# RS485_IO.net
KiCad netlist of a schematic drawn in Altium Designer
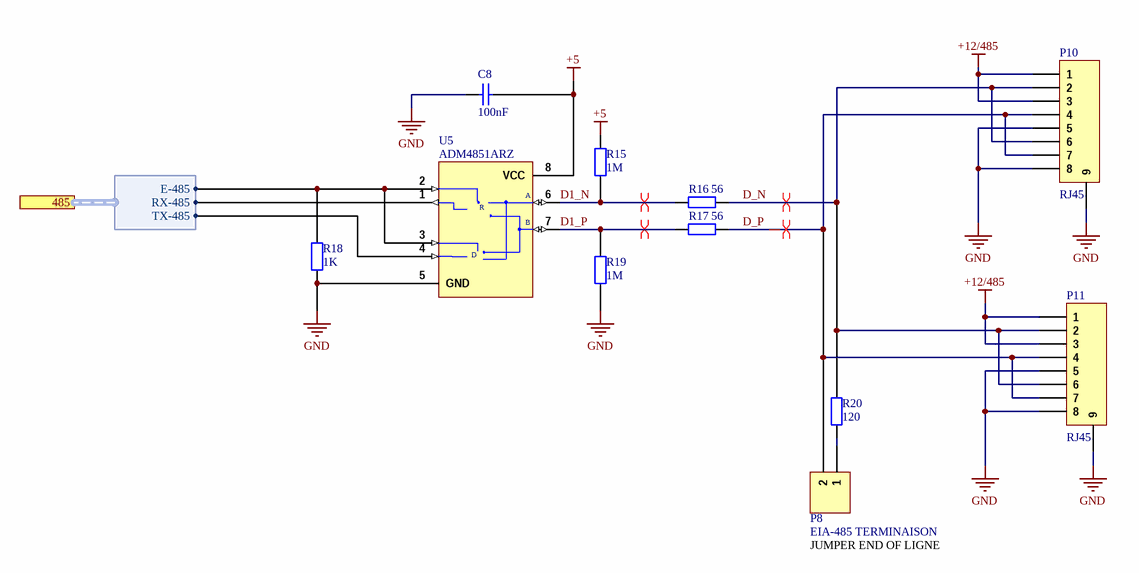
[diagram p0: RS485 IO.SchDoc]

(export (version "E")
  (design (tool "Eeschema 10.0.6"))
  (components
    (comp (ref "C8")
      (value "100nF")
      (footprint "SYLANN:C0805")
      (description "Capacitor")
      (fields
        (field (name "MANUFACTURER") "MULTICOMP")
        (field (name "MANUFACTURER PART NUMBER") "MCCA000296")
      )
      (libsource (lib "BRA") (part "Cap 0805 100nF"))
    )
    (comp (ref "P8")
      (value "EIA-485 TERMINAISON")
      (footprint "M20_1X2")
      (description "Header, 2-Pin")
      (fields
        (field (name "MANUFACTURER") "HARWIN")
        (field (name "MANUFACTURER PART NUMBER") "M20-8770242")
        (field (name "PUBLISHER") "Altium Limited")
      )
      (libsource (lib "Miscellaneous Connectors") (part "Header 2"))
    )
    (comp (ref "P10")
      (value "RJ45")
      (footprint "RJ45_8-5406721-1")
      (description "Header, 8-Pin")
      (fields
        (field (name "MANUFACTURER") "TE CONNECTIVITY / AMP")
        (field (name "MANUFACTURER PART NUMBER") "5406721-1")
      )
      (libsource (lib "MAIN BOARD CERES") (part "Header 8"))
    )
    (comp (ref "P11")
      (value "RJ45")
      (footprint "RJ45_8-5406721-1")
      (description "Header, 8-Pin")
      (fields
        (field (name "MANUFACTURER") "TE CONNECTIVITY / AMP")
        (field (name "MANUFACTURER PART NUMBER") "5406721-1")
      )
      (libsource (lib "MAIN BOARD CERES") (part "Header 8"))
    )
    (comp (ref "R15")
      (value "1M")
      (footprint "R0805")
      (description "Resistor")
      (libsource (lib "BRA") (part "Resistor 0805 1M"))
    )
    (comp (ref "R16")
      (value "56")
      (footprint "R0805")
      (description "Resistor")
      (fields
        (field (name "MANUFACTURER") "MULTICOMP")
        (field (name "MANUFACTURER PART NUMBER") "MC01W0805156R")
      )
      (libsource (lib "BRA") (part "Resistor 0805 56"))
    )
    (comp (ref "R17")
      (value "56")
      (footprint "R0805")
      (description "Resistor")
      (fields
        (field (name "MANUFACTURER") "MULTICOMP")
        (field (name "MANUFACTURER PART NUMBER") "MC01W0805156R")
      )
      (libsource (lib "BRA") (part "Resistor 0805 56"))
    )
    (comp (ref "R18")
      (value "1K")
      (footprint "R0805")
      (description "Resistor")
      (fields
        (field (name "MANUFACTURER") "MULTICOMP")
        (field (name "MANUFACTURER PART NUMBER") "MC0.1W08051%1KFR")
      )
      (libsource (lib "BRA") (part "Resistor 0805 1K"))
    )
    (comp (ref "R19")
      (value "1M")
      (footprint "R0805")
      (description "Resistor")
      (libsource (lib "BRA") (part "Resistor 0805 1M"))
    )
    (comp (ref "R20")
      (value "120")
      (footprint "R0805")
      (description "Resistor")
      (fields
        (field (name "MANUFACTURER") "MULTICOMP")
        (field (name "MANUFACTURER PART NUMBER") "MC01W080516K49")
      )
      (libsource (lib "BRA") (part "Resistor 0805 120"))
    )
    (comp (ref "U5")
      (value "ADM4851ARZ")
      (footprint "SOIC8")
      (description "Low-Power, Slew-Rate-Limited RS-485/RS-422 Transceiver")
      (fields (field (name "MANUFACTURER") "ANALOG DEVICES"))
      (libsource (lib "Maxim Communication Transceiver") (part "MAX485ESA"))
    )
  )
  (nets
    (net (code "2") (name "+5") (class "Default")
      (node (ref "C8") (pin "1") (pinfunction "1_1") (pintype "passive"))
      (node (ref "R15") (pin "2") (pinfunction "2_2") (pintype "passive"))
      (node (ref "U5") (pin "8") (pinfunction "VCC_8") (pintype "power_in"))
    )
    (net (code "3") (name "+12{slash}485") (class "Default")
      (node (ref "P10") (pin "1") (pinfunction "1_1") (pintype "passive"))
      (node (ref "P10") (pin "3") (pinfunction "3_3") (pintype "passive"))
      (node (ref "P11") (pin "1") (pinfunction "1_1") (pintype "passive"))
      (node (ref "P11") (pin "3") (pinfunction "3_3") (pintype "passive"))
    )
    (net (code "4") (name "/D1_N") (class "Default")
      (node (ref "R15") (pin "1") (pinfunction "1_1") (pintype "passive"))
      (node (ref "R16") (pin "1") (pinfunction "1_1") (pintype "passive"))
      (node (ref "U5") (pin "6") (pinfunction "A_6") (pintype "bidirectional"))
    )
    (net (code "5") (name "/D1_P") (class "Default")
      (node (ref "R17") (pin "1") (pinfunction "1_1") (pintype "passive"))
      (node (ref "R19") (pin "2") (pinfunction "2_2") (pintype "passive"))
      (node (ref "U5") (pin "7") (pinfunction "B_7") (pintype "bidirectional"))
    )
    (net (code "6") (name "/D_N") (class "Default")
      (node (ref "P10") (pin "2") (pinfunction "2_2") (pintype "passive"))
      (node (ref "P10") (pin "6") (pinfunction "6_6") (pintype "passive"))
      (node (ref "P11") (pin "2") (pinfunction "2_2") (pintype "passive"))
      (node (ref "P11") (pin "6") (pinfunction "6_6") (pintype "passive"))
      (node (ref "R16") (pin "2") (pinfunction "2_2") (pintype "passive"))
      (node (ref "R20") (pin "2") (pinfunction "2_2") (pintype "passive"))
    )
    (net (code "7") (name "/D_P") (class "Default")
      (node (ref "P10") (pin "4") (pinfunction "4_4") (pintype "passive"))
      (node (ref "P10") (pin "7") (pinfunction "7_7") (pintype "passive"))
      (node (ref "P11") (pin "4") (pinfunction "4_4") (pintype "passive"))
      (node (ref "P11") (pin "7") (pinfunction "7_7") (pintype "passive"))
      (node (ref "P8") (pin "2") (pinfunction "2_2") (pintype "passive"))
      (node (ref "R17") (pin "2") (pinfunction "2_2") (pintype "passive"))
    )
    (net (code "8") (name "/E-485") (class "Default")
      (node (ref "R18") (pin "2") (pinfunction "2_2") (pintype "passive"))
      (node (ref "U5") (pin "2") (pinfunction "~{RE}_2") (pintype "input"))
      (node (ref "U5") (pin "3") (pinfunction "DE_3") (pintype "input"))
    )
    (net (code "9") (name "/RX-485") (class "Default")
      (node (ref "U5") (pin "1") (pinfunction "RO_1") (pintype "output"))
    )
    (net (code "10") (name "/TX-485") (class "Default")
      (node (ref "U5") (pin "4") (pinfunction "DI_4") (pintype "input"))
    )
    (net (code "12") (name "GND") (class "Default")
      (node (ref "C8") (pin "2") (pinfunction "2_2") (pintype "passive"))
      (node (ref "P10") (pin "5") (pinfunction "5_5") (pintype "passive"))
      (node (ref "P10") (pin "8") (pinfunction "8_8") (pintype "passive"))
      (node (ref "P10") (pin "9") (pinfunction "9_9") (pintype "passive"))
      (node (ref "P11") (pin "5") (pinfunction "5_5") (pintype "passive"))
      (node (ref "P11") (pin "8") (pinfunction "8_8") (pintype "passive"))
      (node (ref "P11") (pin "9") (pinfunction "9_9") (pintype "passive"))
      (node (ref "R18") (pin "1") (pinfunction "1_1") (pintype "passive"))
      (node (ref "R19") (pin "1") (pinfunction "1_1") (pintype "passive"))
      (node (ref "U5") (pin "5") (pinfunction "GND_5") (pintype "power_in"))
    )
    (net (code "13") (name "Net-(P8-Pad1)") (class "Default")
      (node (ref "P8") (pin "1") (pinfunction "1_1") (pintype "passive"))
      (node (ref "R20") (pin "1") (pinfunction "1_1") (pintype "passive"))
    )
  )
)
